# ProDoc.net
KiCad netlist of a schematic drawn in EasyEDA Pro
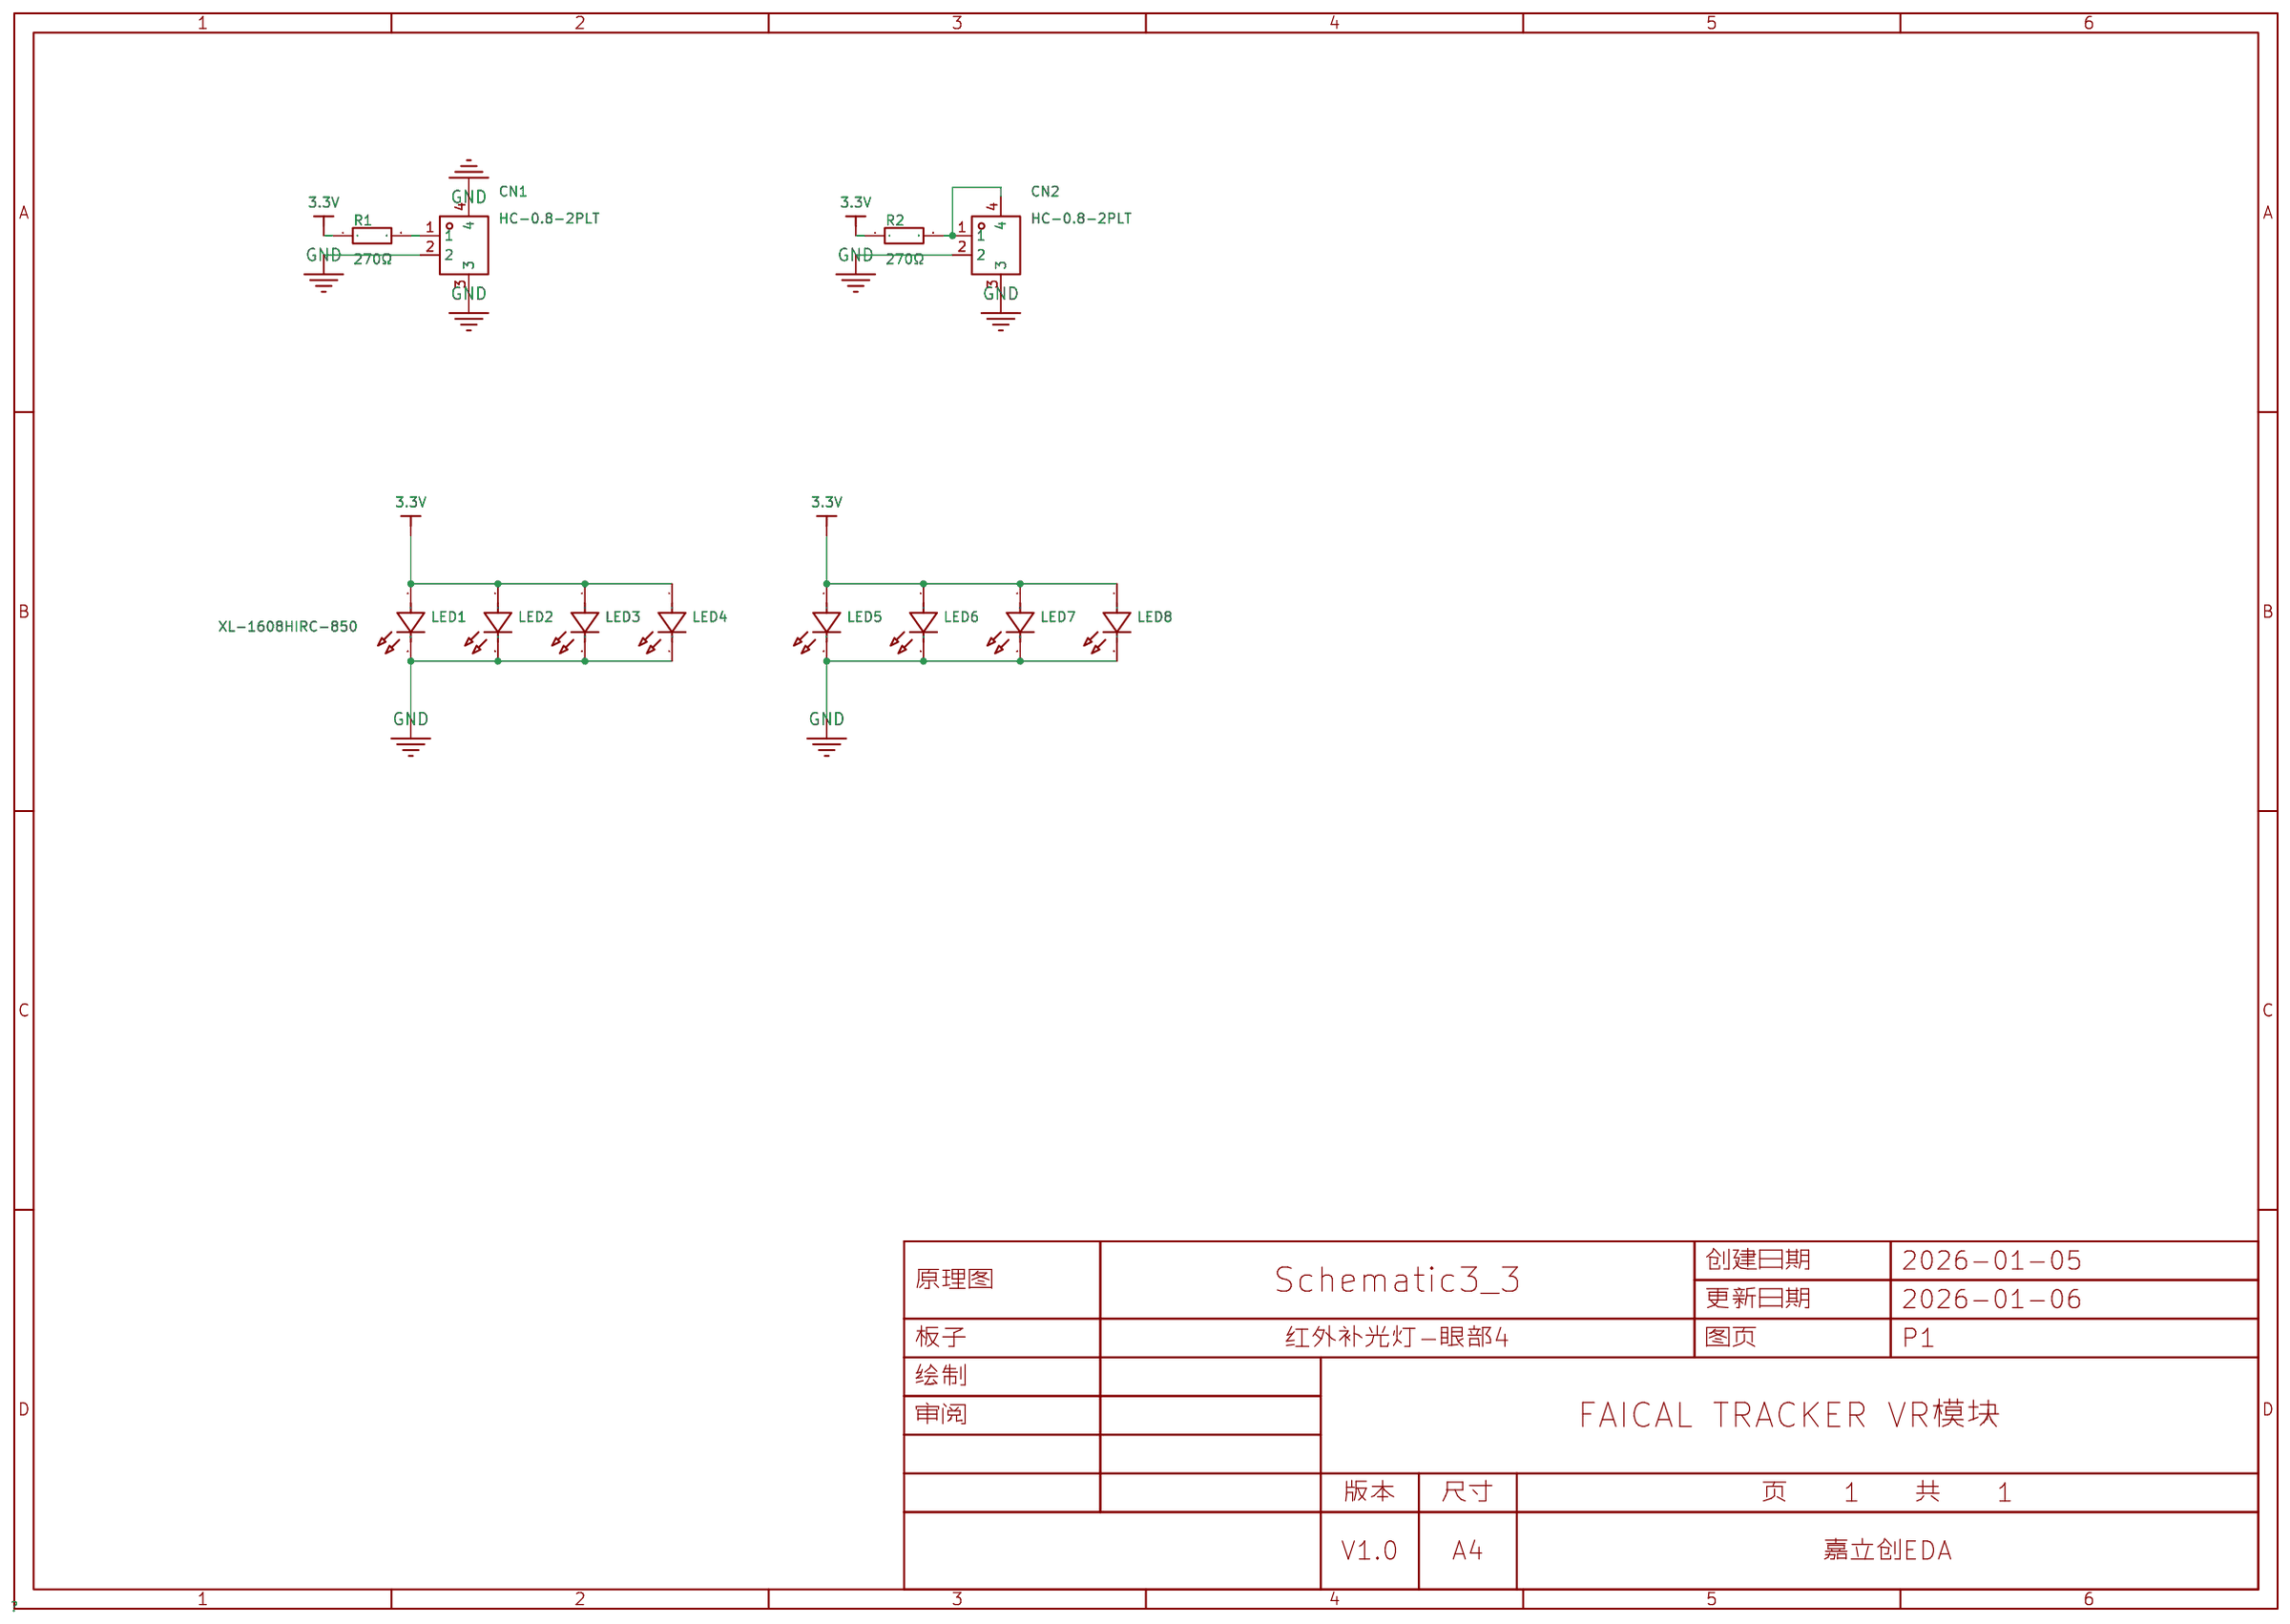
[diagram p0: schematic sheet]

(export (version "E")
  (design (tool "Eeschema 10.0.6"))
  (components
    (comp (ref "CN1")
      (value "HC-0.8-2PLT")
      (footprint "easyedapro:CONN-SMD_2P-P0.80_HCTL_HC-0.8-2PLT")
      (fields (field (name "Manufacturer") "HCTL(华灿天禄)"))
      (libsource (lib "easyedapro") (part "HC-0.8-2PLT"))
    )
    (comp (ref "CN2")
      (value "HC-0.8-2PLT")
      (footprint "easyedapro:CONN-SMD_2P-P0.80_HCTL_HC-0.8-2PLT")
      (fields (field (name "Manufacturer") "HCTL(华灿天禄)"))
      (libsource (lib "easyedapro") (part "HC-0.8-2PLT"))
    )
    (comp (ref "LED1")
      (value "XL-1608HIRC-850")
      (footprint "easyedapro:OPTO-SMD_L1.6-W0.80-RD_XL-1608HIRC-850")
      (fields (field (name "Manufacturer") "XINGLIGHT(成兴光)"))
      (libsource (lib "easyedapro") (part "XL-1608HIRC-850"))
    )
    (comp (ref "LED2")
      (value "XL-1608HIRC-850")
      (footprint "easyedapro:OPTO-SMD_L1.6-W0.80-RD_XL-1608HIRC-850")
      (fields (field (name "Manufacturer") "XINGLIGHT(成兴光)"))
      (libsource (lib "easyedapro") (part "XL-1608HIRC-850"))
    )
    (comp (ref "LED3")
      (value "XL-1608HIRC-850")
      (footprint "easyedapro:OPTO-SMD_L1.6-W0.80-RD_XL-1608HIRC-850")
      (fields (field (name "Manufacturer") "XINGLIGHT(成兴光)"))
      (libsource (lib "easyedapro") (part "XL-1608HIRC-850"))
    )
    (comp (ref "LED4")
      (value "XL-1608HIRC-850")
      (footprint "easyedapro:OPTO-SMD_L1.6-W0.80-RD_XL-1608HIRC-850")
      (fields (field (name "Manufacturer") "XINGLIGHT(成兴光)"))
      (libsource (lib "easyedapro") (part "XL-1608HIRC-850"))
    )
    (comp (ref "LED5")
      (value "XL-1608HIRC-850")
      (footprint "easyedapro:OPTO-SMD_L1.6-W0.80-RD_XL-1608HIRC-850")
      (fields (field (name "Manufacturer") "XINGLIGHT(成兴光)"))
      (libsource (lib "easyedapro") (part "XL-1608HIRC-850"))
    )
    (comp (ref "LED6")
      (value "XL-1608HIRC-850")
      (footprint "easyedapro:OPTO-SMD_L1.6-W0.80-RD_XL-1608HIRC-850")
      (fields (field (name "Manufacturer") "XINGLIGHT(成兴光)"))
      (libsource (lib "easyedapro") (part "XL-1608HIRC-850"))
    )
    (comp (ref "LED7")
      (value "XL-1608HIRC-850")
      (footprint "easyedapro:OPTO-SMD_L1.6-W0.80-RD_XL-1608HIRC-850")
      (fields (field (name "Manufacturer") "XINGLIGHT(成兴光)"))
      (libsource (lib "easyedapro") (part "XL-1608HIRC-850"))
    )
    (comp (ref "LED8")
      (value "XL-1608HIRC-850")
      (footprint "easyedapro:OPTO-SMD_L1.6-W0.80-RD_XL-1608HIRC-850")
      (fields (field (name "Manufacturer") "XINGLIGHT(成兴光)"))
      (libsource (lib "easyedapro") (part "XL-1608HIRC-850"))
    )
    (comp (ref "R1")
      (value "270Ω")
      (description "电阻类型:厚膜电阻;阻值:270Ω;精度:±1%;功率:100mW;工作电压:75V;温度系数:±100ppm/℃;")
      (fields
        (field (name "Manufacturer Part") "0603WAF2700T5E")
        (field (name "Manufacturer") "UNI-ROYAL(厚声)")
      )
      (libsource (lib "easyedapro") (part "0603WAF2000T5E"))
    )
    (comp (ref "R2")
      (value "270Ω")
      (description "电阻类型:厚膜电阻;阻值:270Ω;精度:±1%;功率:100mW;工作电压:75V;温度系数:±100ppm/℃;")
      (fields
        (field (name "Manufacturer Part") "0603WAF2700T5E")
        (field (name "Manufacturer") "UNI-ROYAL(厚声)")
      )
      (libsource (lib "easyedapro") (part "0603WAF2000T5E"))
    )
  )
  (nets
    (net (code "1") (name "3.3V") (class "Default")
      (node (ref "LED1") (pin "1") (pinfunction "A_1") (pintype "unspecified"))
      (node (ref "LED2") (pin "1") (pinfunction "A_1") (pintype "unspecified"))
      (node (ref "LED3") (pin "1") (pinfunction "A_1") (pintype "unspecified"))
      (node (ref "LED4") (pin "1") (pinfunction "A_1") (pintype "unspecified"))
      (node (ref "LED5") (pin "1") (pinfunction "A_1") (pintype "unspecified"))
      (node (ref "LED6") (pin "1") (pinfunction "A_1") (pintype "unspecified"))
      (node (ref "LED7") (pin "1") (pinfunction "A_1") (pintype "unspecified"))
      (node (ref "LED8") (pin "1") (pinfunction "A_1") (pintype "unspecified"))
      (node (ref "R1") (pin "1") (pinfunction "1_1") (pintype "input"))
      (node (ref "R2") (pin "1") (pinfunction "1_1") (pintype "input"))
    )
    (net (code "2") (name "GND") (class "Default")
      (node (ref "CN1") (pin "2") (pinfunction "2_2") (pintype "unspecified"))
      (node (ref "CN1") (pin "3") (pinfunction "3_3") (pintype "unspecified"))
      (node (ref "CN1") (pin "4") (pinfunction "4_4") (pintype "unspecified"))
      (node (ref "CN2") (pin "2") (pinfunction "2_2") (pintype "unspecified"))
      (node (ref "CN2") (pin "3") (pinfunction "3_3") (pintype "unspecified"))
      (node (ref "LED1") (pin "2") (pinfunction "C_2") (pintype "unspecified"))
      (node (ref "LED2") (pin "2") (pinfunction "C_2") (pintype "unspecified"))
      (node (ref "LED3") (pin "2") (pinfunction "C_2") (pintype "unspecified"))
      (node (ref "LED4") (pin "2") (pinfunction "C_2") (pintype "unspecified"))
      (node (ref "LED5") (pin "2") (pinfunction "C_2") (pintype "unspecified"))
      (node (ref "LED6") (pin "2") (pinfunction "C_2") (pintype "unspecified"))
      (node (ref "LED7") (pin "2") (pinfunction "C_2") (pintype "unspecified"))
      (node (ref "LED8") (pin "2") (pinfunction "C_2") (pintype "unspecified"))
    )
    (net (code "3") (name "Net-(CN1-Pad1)") (class "Default")
      (node (ref "CN1") (pin "1") (pinfunction "1_1") (pintype "unspecified"))
      (node (ref "R1") (pin "2") (pinfunction "2_2") (pintype "input"))
    )
    (net (code "4") (name "Net-(CN2-Pad1)") (class "Default")
      (node (ref "CN2") (pin "1") (pinfunction "1_1") (pintype "unspecified"))
      (node (ref "CN2") (pin "4") (pinfunction "4_4") (pintype "unspecified"))
      (node (ref "R2") (pin "2") (pinfunction "2_2") (pintype "input"))
    )
  )
)
